# modul_L298.net
KiCad netlist of a schematic drawn in Altium Designer
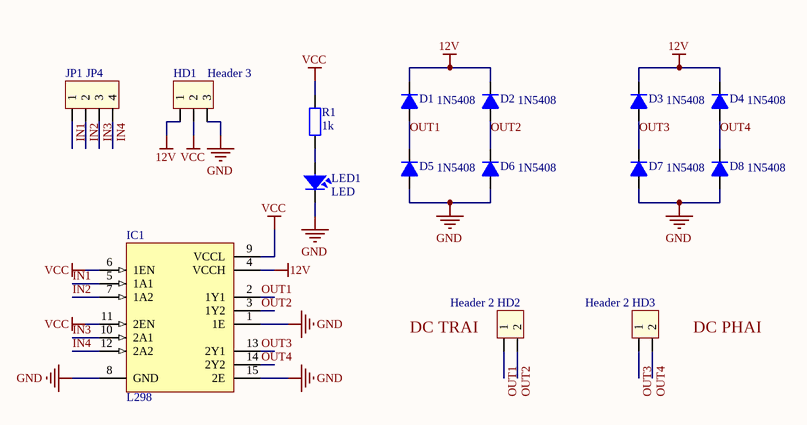
[diagram p0: modul L298.SchDoc]

(export (version "E")
  (design (tool "Eeschema 10.0.6"))
  (components
    (comp (ref "D1")
      (value "1N5408")
      (footprint "D5A")
      (description "Diode 5A")
      (libsource (lib "syhaunguyen") (part "D5A"))
    )
    (comp (ref "D2")
      (value "1N5408")
      (footprint "D5A")
      (description "Diode 5A")
      (libsource (lib "syhaunguyen") (part "D5A"))
    )
    (comp (ref "D3")
      (value "1N5408")
      (footprint "D5A")
      (description "Diode 5A")
      (libsource (lib "syhaunguyen") (part "D5A"))
    )
    (comp (ref "D4")
      (value "1N5408")
      (footprint "D5A")
      (description "Diode 5A")
      (libsource (lib "syhaunguyen") (part "D5A"))
    )
    (comp (ref "D5")
      (value "1N5408")
      (footprint "D5A")
      (description "Diode 5A")
      (libsource (lib "syhaunguyen") (part "D5A"))
    )
    (comp (ref "D6")
      (value "1N5408")
      (footprint "D5A")
      (description "Diode 5A")
      (libsource (lib "syhaunguyen") (part "D5A"))
    )
    (comp (ref "D7")
      (value "1N5408")
      (footprint "D5A")
      (description "Diode 5A")
      (libsource (lib "syhaunguyen") (part "D5A"))
    )
    (comp (ref "D8")
      (value "1N5408")
      (footprint "D5A")
      (description "Diode 5A")
      (libsource (lib "syhaunguyen") (part "D5A"))
    )
    (comp (ref "HD1")
      (value "Header 3")
      (footprint "HED3")
      (description "Header 3 (Green)")
      (libsource (lib "syhaunguyen") (part "Hed3"))
    )
    (comp (ref "HD2")
      (value "Header 2")
      (footprint "HED2")
      (description "Header 2 (Green)")
      (libsource (lib "syhaunguyen") (part "Hed2"))
    )
    (comp (ref "HD3")
      (value "Header 2")
      (footprint "HED2")
      (description "Header 2 (Green)")
      (libsource (lib "syhaunguyen") (part "Hed2"))
    )
    (comp (ref "IC1")
      (value "L298")
      (footprint "DIP15SL2")
      (description "Dual Full-H Driver")
      (fields (field (name "PUBLISHER") "Altium Limited"))
      (libsource (lib "syhaunguyen") (part "L298"))
    )
    (comp (ref "JP1")
      (value "JP4")
      (footprint "CON4")
      (description "Connector 4")
      (libsource (lib "syhaunguyen") (part "Con4"))
    )
    (comp (ref "LED1")
      (value "LED")
      (footprint "LED-3")
      (description "Led  Vuong")
      (libsource (lib "syhaunguyen") (part "LED"))
    )
    (comp (ref "R1")
      (value "1k")
      (footprint "R1/4W")
      (description "Resistor 1/4W")
      (libsource (lib "syhaunguyen") (part "R1/4W"))
    )
  )
  (nets
    (net (code "3") (name "/IN1") (class "Default")
      (node (ref "IC1") (pin "5") (pinfunction "1A1_5") (pintype "input"))
      (node (ref "JP1") (pin "1") (pinfunction "1_1") (pintype "passive"))
    )
    (net (code "4") (name "/IN2") (class "Default")
      (node (ref "IC1") (pin "7") (pinfunction "1A2_7") (pintype "input"))
      (node (ref "JP1") (pin "2") (pinfunction "2_2") (pintype "passive"))
    )
    (net (code "5") (name "/IN3") (class "Default")
      (node (ref "IC1") (pin "10") (pinfunction "2A1_10") (pintype "input"))
      (node (ref "JP1") (pin "3") (pinfunction "3_3") (pintype "passive"))
    )
    (net (code "6") (name "/IN4") (class "Default")
      (node (ref "IC1") (pin "12") (pinfunction "2A2_12") (pintype "input"))
      (node (ref "JP1") (pin "4") (pinfunction "4_4") (pintype "passive"))
    )
    (net (code "7") (name "/OUT1") (class "Default")
      (node (ref "D1") (pin "1") (pinfunction "A_1") (pintype "passive"))
      (node (ref "D5") (pin "2") (pinfunction "K_2") (pintype "passive"))
      (node (ref "HD2") (pin "1") (pinfunction "1_1") (pintype "passive"))
      (node (ref "IC1") (pin "2") (pinfunction "1Y1_2") (pintype "tri_state"))
    )
    (net (code "8") (name "/OUT2") (class "Default")
      (node (ref "D2") (pin "1") (pinfunction "A_1") (pintype "passive"))
      (node (ref "D6") (pin "2") (pinfunction "K_2") (pintype "passive"))
      (node (ref "HD2") (pin "2") (pinfunction "2_2") (pintype "passive"))
      (node (ref "IC1") (pin "3") (pinfunction "1Y2_3") (pintype "tri_state"))
    )
    (net (code "9") (name "/OUT3") (class "Default")
      (node (ref "D3") (pin "1") (pinfunction "A_1") (pintype "passive"))
      (node (ref "D7") (pin "2") (pinfunction "K_2") (pintype "passive"))
      (node (ref "HD3") (pin "1") (pinfunction "1_1") (pintype "passive"))
      (node (ref "IC1") (pin "13") (pinfunction "2Y1_13") (pintype "tri_state"))
    )
    (net (code "10") (name "/OUT4") (class "Default")
      (node (ref "D4") (pin "1") (pinfunction "A_1") (pintype "passive"))
      (node (ref "D8") (pin "2") (pinfunction "K_2") (pintype "passive"))
      (node (ref "HD3") (pin "2") (pinfunction "2_2") (pintype "passive"))
      (node (ref "IC1") (pin "14") (pinfunction "2Y2_14") (pintype "tri_state"))
    )
    (net (code "11") (name "12V") (class "Default")
      (node (ref "D1") (pin "2") (pinfunction "K_2") (pintype "passive"))
      (node (ref "D2") (pin "2") (pinfunction "K_2") (pintype "passive"))
      (node (ref "D3") (pin "2") (pinfunction "K_2") (pintype "passive"))
      (node (ref "D4") (pin "2") (pinfunction "K_2") (pintype "passive"))
      (node (ref "HD1") (pin "1") (pinfunction "1_1") (pintype "passive"))
      (node (ref "IC1") (pin "4") (pinfunction "VCCH_4") (pintype "power_in"))
    )
    (net (code "12") (name "GND") (class "Default")
      (node (ref "D5") (pin "1") (pinfunction "A_1") (pintype "passive"))
      (node (ref "D6") (pin "1") (pinfunction "A_1") (pintype "passive"))
      (node (ref "D7") (pin "1") (pinfunction "A_1") (pintype "passive"))
      (node (ref "D8") (pin "1") (pinfunction "A_1") (pintype "passive"))
      (node (ref "HD1") (pin "3") (pinfunction "3_3") (pintype "passive"))
      (node (ref "IC1") (pin "1") (pinfunction "1E_1") (pintype "passive"))
      (node (ref "IC1") (pin "15") (pinfunction "2E_15") (pintype "passive"))
      (node (ref "IC1") (pin "8") (pinfunction "GND_8") (pintype "power_in"))
      (node (ref "LED1") (pin "2") (pinfunction "2_2") (pintype "passive"))
    )
    (net (code "13") (name "Net-(LED1-Pad1)") (class "Default")
      (node (ref "LED1") (pin "1") (pinfunction "1_1") (pintype "passive"))
      (node (ref "R1") (pin "1") (pinfunction "1_1") (pintype "passive"))
    )
    (net (code "14") (name "VCC") (class "Default")
      (node (ref "HD1") (pin "2") (pinfunction "2_2") (pintype "passive"))
      (node (ref "IC1") (pin "11") (pinfunction "2EN_11") (pintype "input"))
      (node (ref "IC1") (pin "6") (pinfunction "1EN_6") (pintype "input"))
      (node (ref "IC1") (pin "9") (pinfunction "VCCL_9") (pintype "power_in"))
      (node (ref "R1") (pin "2") (pinfunction "2_2") (pintype "passive"))
    )
  )
)
